# Sheet2.net
KiCad netlist of a schematic drawn in Altium Designer
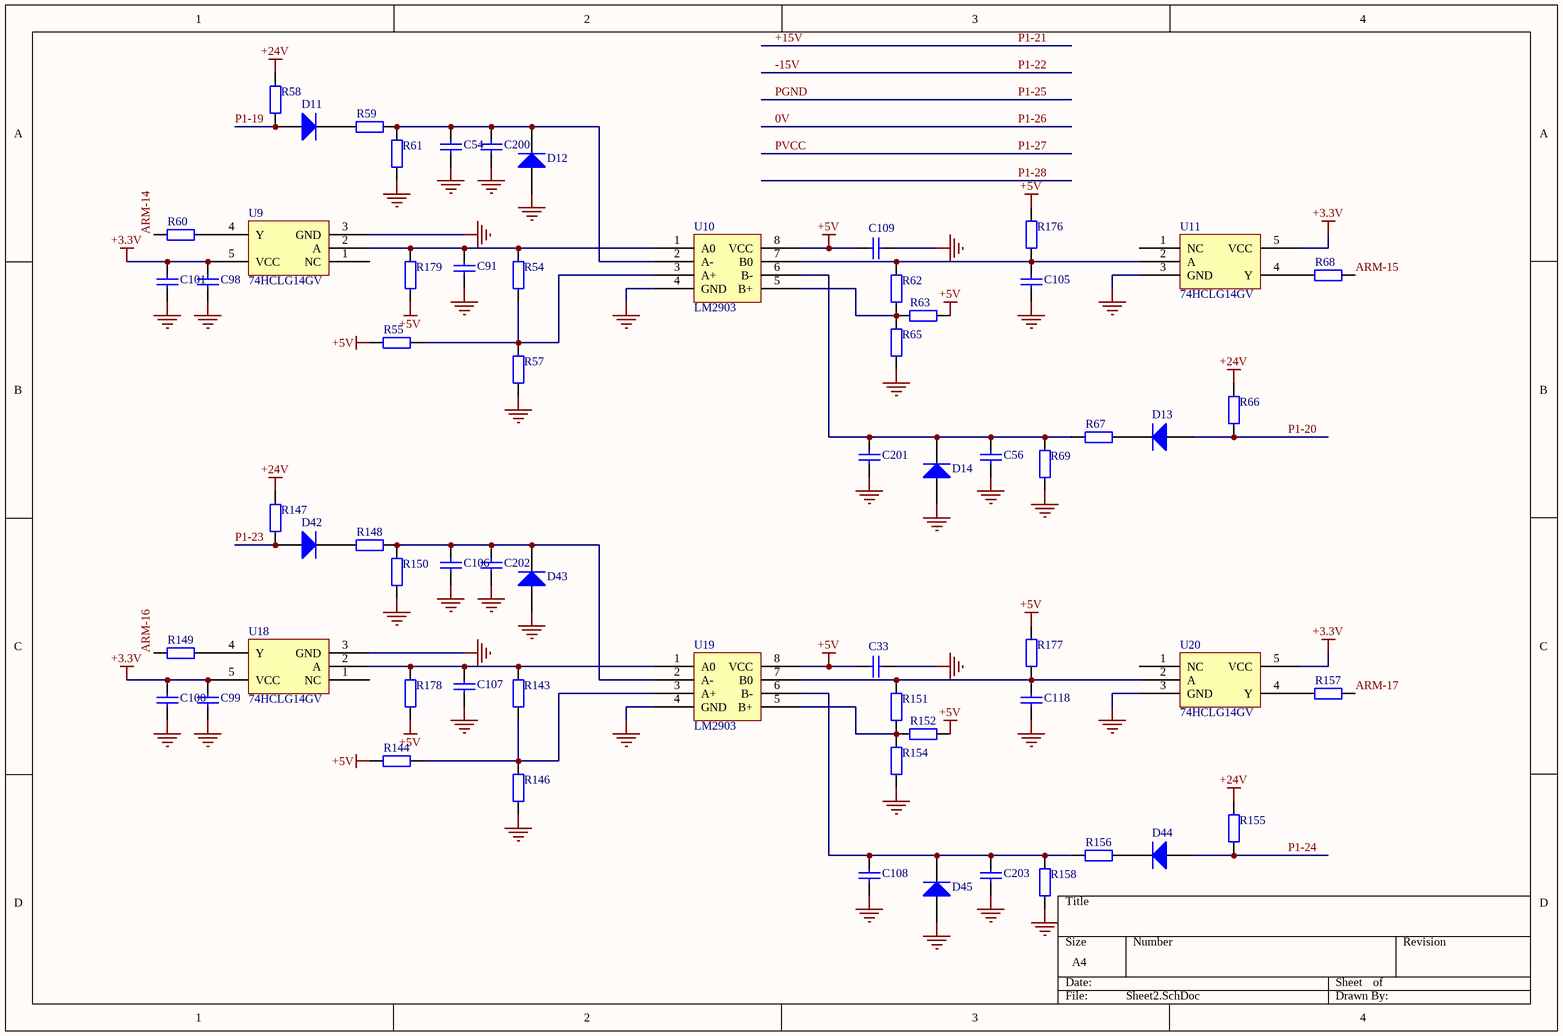
[diagram p0: Sheet2.SchDoc]

(export (version "E")
  (design (tool "Eeschema 10.0.6"))
  (components
    (comp (ref "C33")
      (value "Cap")
      (footprint "RAD-0.3")
      (description "Capacitor")
      (fields (field (name "PUBLISHER") "Altium Limited"))
      (libsource (lib "Miscellaneous Devices") (part "Cap"))
    )
    (comp (ref "C54")
      (value "Cap")
      (footprint "RAD-0.3")
      (description "Capacitor")
      (fields (field (name "PUBLISHER") "Altium Limited"))
      (libsource (lib "Miscellaneous Devices") (part "Cap"))
    )
    (comp (ref "C56")
      (value "Cap")
      (footprint "RAD-0.3")
      (description "Capacitor")
      (fields (field (name "PUBLISHER") "Altium Limited"))
      (libsource (lib "Miscellaneous Devices") (part "Cap"))
    )
    (comp (ref "C91")
      (value "Cap")
      (footprint "RAD-0.3")
      (description "Capacitor")
      (fields (field (name "PUBLISHER") "Altium Limited"))
      (libsource (lib "Miscellaneous Devices") (part "Cap"))
    )
    (comp (ref "C98")
      (value "Cap")
      (footprint "RAD-0.3")
      (description "Capacitor")
      (fields (field (name "PUBLISHER") "Altium Limited"))
      (libsource (lib "Miscellaneous Devices") (part "Cap"))
    )
    (comp (ref "C99")
      (value "Cap")
      (footprint "RAD-0.3")
      (description "Capacitor")
      (fields (field (name "PUBLISHER") "Altium Limited"))
      (libsource (lib "Miscellaneous Devices") (part "Cap"))
    )
    (comp (ref "C100")
      (value "Cap")
      (footprint "RAD-0.3")
      (description "Capacitor")
      (fields (field (name "PUBLISHER") "Altium Limited"))
      (libsource (lib "Miscellaneous Devices") (part "Cap"))
    )
    (comp (ref "C101")
      (value "Cap")
      (footprint "RAD-0.3")
      (description "Capacitor")
      (fields (field (name "PUBLISHER") "Altium Limited"))
      (libsource (lib "Miscellaneous Devices") (part "Cap"))
    )
    (comp (ref "C105")
      (value "Cap")
      (footprint "RAD-0.3")
      (description "Capacitor")
      (fields (field (name "PUBLISHER") "Altium Limited"))
      (libsource (lib "Miscellaneous Devices") (part "Cap"))
    )
    (comp (ref "C106")
      (value "Cap")
      (footprint "RAD-0.3")
      (description "Capacitor")
      (fields (field (name "PUBLISHER") "Altium Limited"))
      (libsource (lib "Miscellaneous Devices") (part "Cap"))
    )
    (comp (ref "C107")
      (value "Cap")
      (footprint "RAD-0.3")
      (description "Capacitor")
      (fields (field (name "PUBLISHER") "Altium Limited"))
      (libsource (lib "Miscellaneous Devices") (part "Cap"))
    )
    (comp (ref "C108")
      (value "Cap")
      (footprint "RAD-0.3")
      (description "Capacitor")
      (fields (field (name "PUBLISHER") "Altium Limited"))
      (libsource (lib "Miscellaneous Devices") (part "Cap"))
    )
    (comp (ref "C109")
      (value "Cap")
      (footprint "RAD-0.3")
      (description "Capacitor")
      (fields (field (name "PUBLISHER") "Altium Limited"))
      (libsource (lib "Miscellaneous Devices") (part "Cap"))
    )
    (comp (ref "C118")
      (value "Cap")
      (footprint "RAD-0.3")
      (description "Capacitor")
      (fields (field (name "PUBLISHER") "Altium Limited"))
      (libsource (lib "Miscellaneous Devices") (part "Cap"))
    )
    (comp (ref "C200")
      (value "Cap")
      (footprint "RAD-0.3")
      (description "Capacitor")
      (fields (field (name "PUBLISHER") "Altium Limited"))
      (libsource (lib "Miscellaneous Devices") (part "Cap"))
    )
    (comp (ref "C201")
      (value "Cap")
      (footprint "RAD-0.3")
      (description "Capacitor")
      (fields (field (name "PUBLISHER") "Altium Limited"))
      (libsource (lib "Miscellaneous Devices") (part "Cap"))
    )
    (comp (ref "C202")
      (value "Cap")
      (footprint "RAD-0.3")
      (description "Capacitor")
      (fields (field (name "PUBLISHER") "Altium Limited"))
      (libsource (lib "Miscellaneous Devices") (part "Cap"))
    )
    (comp (ref "C203")
      (value "Cap")
      (footprint "RAD-0.3")
      (description "Capacitor")
      (fields (field (name "PUBLISHER") "Altium Limited"))
      (libsource (lib "Miscellaneous Devices") (part "Cap"))
    )
    (comp (ref "D11")
      (value "Diode 1N4007")
      (footprint "DO-41")
      (description "1 Amp General Purpose Rectifier")
      (fields (field (name "PUBLISHER") "Altium Limited"))
      (libsource (lib "Miscellaneous Devices") (part "Diode 1N4007"))
    )
    (comp (ref "D12")
      (value "Diode 1N4007")
      (footprint "DO-41")
      (description "1 Amp General Purpose Rectifier")
      (fields (field (name "PUBLISHER") "Altium Limited"))
      (libsource (lib "Miscellaneous Devices") (part "Diode 1N4007"))
    )
    (comp (ref "D13")
      (value "Diode 1N4007")
      (footprint "DO-41")
      (description "1 Amp General Purpose Rectifier")
      (fields (field (name "PUBLISHER") "Altium Limited"))
      (libsource (lib "Miscellaneous Devices") (part "Diode 1N4007"))
    )
    (comp (ref "D14")
      (value "Diode 1N4007")
      (footprint "DO-41")
      (description "1 Amp General Purpose Rectifier")
      (fields (field (name "PUBLISHER") "Altium Limited"))
      (libsource (lib "Miscellaneous Devices") (part "Diode 1N4007"))
    )
    (comp (ref "D42")
      (value "Diode 1N4007")
      (footprint "DO-41")
      (description "1 Amp General Purpose Rectifier")
      (fields (field (name "PUBLISHER") "Altium Limited"))
      (libsource (lib "Miscellaneous Devices") (part "Diode 1N4007"))
    )
    (comp (ref "D43")
      (value "Diode 1N4007")
      (footprint "DO-41")
      (description "1 Amp General Purpose Rectifier")
      (fields (field (name "PUBLISHER") "Altium Limited"))
      (libsource (lib "Miscellaneous Devices") (part "Diode 1N4007"))
    )
    (comp (ref "D44")
      (value "Diode 1N4007")
      (footprint "DO-41")
      (description "1 Amp General Purpose Rectifier")
      (fields (field (name "PUBLISHER") "Altium Limited"))
      (libsource (lib "Miscellaneous Devices") (part "Diode 1N4007"))
    )
    (comp (ref "D45")
      (value "Diode 1N4007")
      (footprint "DO-41")
      (description "1 Amp General Purpose Rectifier")
      (fields (field (name "PUBLISHER") "Altium Limited"))
      (libsource (lib "Miscellaneous Devices") (part "Diode 1N4007"))
    )
    (comp (ref "R54")
      (value "Res2")
      (footprint "AXIAL-0.4")
      (description "Resistor")
      (fields (field (name "PUBLISHER") "Altium Limited"))
      (libsource (lib "") (part "Res2_1"))
    )
    (comp (ref "R55")
      (value "Res2")
      (footprint "AXIAL-0.4")
      (description "Resistor")
      (fields (field (name "PUBLISHER") "Altium Limited"))
      (libsource (lib "") (part "Res2_2"))
    )
    (comp (ref "R57")
      (value "Res2")
      (footprint "AXIAL-0.4")
      (description "Resistor")
      (fields (field (name "PUBLISHER") "Altium Limited"))
      (libsource (lib "Miscellaneous Devices") (part "Res2"))
    )
    (comp (ref "R58")
      (value "Res2")
      (footprint "AXIAL-0.4")
      (description "Resistor")
      (fields (field (name "PUBLISHER") "Altium Limited"))
      (libsource (lib "") (part "Res2_1"))
    )
    (comp (ref "R59")
      (value "Res2")
      (footprint "AXIAL-0.4")
      (description "Resistor")
      (fields (field (name "PUBLISHER") "Altium Limited"))
      (libsource (lib "") (part "Res2_2"))
    )
    (comp (ref "R60")
      (value "Res2")
      (footprint "AXIAL-0.4")
      (description "Resistor")
      (fields (field (name "PUBLISHER") "Altium Limited"))
      (libsource (lib "") (part "Res2_3"))
    )
    (comp (ref "R61")
      (value "Res2")
      (footprint "AXIAL-0.4")
      (description "Resistor")
      (fields (field (name "PUBLISHER") "Altium Limited"))
      (libsource (lib "") (part "Res2_1"))
    )
    (comp (ref "R62")
      (value "Res2")
      (footprint "AXIAL-0.4")
      (description "Resistor")
      (fields (field (name "PUBLISHER") "Altium Limited"))
      (libsource (lib "Miscellaneous Devices") (part "Res2"))
    )
    (comp (ref "R63")
      (value "Res2")
      (footprint "AXIAL-0.4")
      (description "Resistor")
      (fields (field (name "PUBLISHER") "Altium Limited"))
      (libsource (lib "") (part "Res2_2"))
    )
    (comp (ref "R65")
      (value "Res2")
      (footprint "AXIAL-0.4")
      (description "Resistor")
      (fields (field (name "PUBLISHER") "Altium Limited"))
      (libsource (lib "Miscellaneous Devices") (part "Res2"))
    )
    (comp (ref "R66")
      (value "Res2")
      (footprint "AXIAL-0.4")
      (description "Resistor")
      (fields (field (name "PUBLISHER") "Altium Limited"))
      (libsource (lib "") (part "Res2_1"))
    )
    (comp (ref "R67")
      (value "Res2")
      (footprint "AXIAL-0.4")
      (description "Resistor")
      (fields (field (name "PUBLISHER") "Altium Limited"))
      (libsource (lib "") (part "Res2_2"))
    )
    (comp (ref "R68")
      (value "Res2")
      (footprint "AXIAL-0.4")
      (description "Resistor")
      (fields (field (name "PUBLISHER") "Altium Limited"))
      (libsource (lib "") (part "Res2_3"))
    )
    (comp (ref "R69")
      (value "Res2")
      (footprint "AXIAL-0.4")
      (description "Resistor")
      (fields (field (name "PUBLISHER") "Altium Limited"))
      (libsource (lib "") (part "Res2_1"))
    )
    (comp (ref "R143")
      (value "Res2")
      (footprint "AXIAL-0.4")
      (description "Resistor")
      (fields (field (name "PUBLISHER") "Altium Limited"))
      (libsource (lib "") (part "Res2_1"))
    )
    (comp (ref "R144")
      (value "Res2")
      (footprint "AXIAL-0.4")
      (description "Resistor")
      (fields (field (name "PUBLISHER") "Altium Limited"))
      (libsource (lib "") (part "Res2_2"))
    )
    (comp (ref "R146")
      (value "Res2")
      (footprint "AXIAL-0.4")
      (description "Resistor")
      (fields (field (name "PUBLISHER") "Altium Limited"))
      (libsource (lib "Miscellaneous Devices") (part "Res2"))
    )
    (comp (ref "R147")
      (value "Res2")
      (footprint "AXIAL-0.4")
      (description "Resistor")
      (fields (field (name "PUBLISHER") "Altium Limited"))
      (libsource (lib "") (part "Res2_1"))
    )
    (comp (ref "R148")
      (value "Res2")
      (footprint "AXIAL-0.4")
      (description "Resistor")
      (fields (field (name "PUBLISHER") "Altium Limited"))
      (libsource (lib "") (part "Res2_2"))
    )
    (comp (ref "R149")
      (value "Res2")
      (footprint "AXIAL-0.4")
      (description "Resistor")
      (fields (field (name "PUBLISHER") "Altium Limited"))
      (libsource (lib "") (part "Res2_3"))
    )
    (comp (ref "R150")
      (value "Res2")
      (footprint "AXIAL-0.4")
      (description "Resistor")
      (fields (field (name "PUBLISHER") "Altium Limited"))
      (libsource (lib "") (part "Res2_1"))
    )
    (comp (ref "R151")
      (value "Res2")
      (footprint "AXIAL-0.4")
      (description "Resistor")
      (fields (field (name "PUBLISHER") "Altium Limited"))
      (libsource (lib "Miscellaneous Devices") (part "Res2"))
    )
    (comp (ref "R152")
      (value "Res2")
      (footprint "AXIAL-0.4")
      (description "Resistor")
      (fields (field (name "PUBLISHER") "Altium Limited"))
      (libsource (lib "") (part "Res2_2"))
    )
    (comp (ref "R154")
      (value "Res2")
      (footprint "AXIAL-0.4")
      (description "Resistor")
      (fields (field (name "PUBLISHER") "Altium Limited"))
      (libsource (lib "Miscellaneous Devices") (part "Res2"))
    )
    (comp (ref "R155")
      (value "Res2")
      (footprint "AXIAL-0.4")
      (description "Resistor")
      (fields (field (name "PUBLISHER") "Altium Limited"))
      (libsource (lib "") (part "Res2_1"))
    )
    (comp (ref "R156")
      (value "Res2")
      (footprint "AXIAL-0.4")
      (description "Resistor")
      (fields (field (name "PUBLISHER") "Altium Limited"))
      (libsource (lib "") (part "Res2_2"))
    )
    (comp (ref "R157")
      (value "Res2")
      (footprint "AXIAL-0.4")
      (description "Resistor")
      (fields (field (name "PUBLISHER") "Altium Limited"))
      (libsource (lib "") (part "Res2_3"))
    )
    (comp (ref "R158")
      (value "Res2")
      (footprint "AXIAL-0.4")
      (description "Resistor")
      (fields (field (name "PUBLISHER") "Altium Limited"))
      (libsource (lib "") (part "Res2_1"))
    )
    (comp (ref "R176")
      (value "Res2")
      (footprint "AXIAL-0.4")
      (description "Resistor")
      (fields (field (name "PUBLISHER") "Altium Limited"))
      (libsource (lib "Miscellaneous Devices") (part "Res2"))
    )
    (comp (ref "R177")
      (value "Res2")
      (footprint "AXIAL-0.4")
      (description "Resistor")
      (fields (field (name "PUBLISHER") "Altium Limited"))
      (libsource (lib "Miscellaneous Devices") (part "Res2"))
    )
    (comp (ref "R178")
      (value "Res2")
      (footprint "AXIAL-0.4")
      (description "Resistor")
      (fields (field (name "PUBLISHER") "Altium Limited"))
      (libsource (lib "Miscellaneous Devices") (part "Res2"))
    )
    (comp (ref "R179")
      (value "Res2")
      (footprint "AXIAL-0.4")
      (description "Resistor")
      (fields (field (name "PUBLISHER") "Altium Limited"))
      (libsource (lib "Miscellaneous Devices") (part "Res2"))
    )
    (comp (ref "U9") (value "74HCLG14GV") (libsource (lib "Schlib1") (part "Component_1")))
    (comp (ref "U10") (value "LM2903") (libsource (lib "LM2903") (part "Component_1")))
    (comp (ref "U11") (value "74HCLG14GV") (libsource (lib "") (part "Component_1_1")))
    (comp (ref "U18") (value "74HCLG14GV") (libsource (lib "Schlib1") (part "Component_1")))
    (comp (ref "U19") (value "LM2903") (libsource (lib "LM2903") (part "Component_1")))
    (comp (ref "U20") (value "74HCLG14GV") (libsource (lib "") (part "Component_1_1")))
  )
  (nets
    (net (code "1") (name "+3.3V") (class "Default")
      (node (ref "C100") (pin "2") (pinfunction "2_2") (pintype "passive"))
      (node (ref "C101") (pin "2") (pinfunction "2_2") (pintype "passive"))
      (node (ref "C98") (pin "2") (pinfunction "2_2") (pintype "passive"))
      (node (ref "C99") (pin "2") (pinfunction "2_2") (pintype "passive"))
      (node (ref "U11") (pin "5") (pinfunction "VCC_5") (pintype "passive"))
      (node (ref "U18") (pin "5") (pinfunction "VCC_5") (pintype "passive"))
      (node (ref "U20") (pin "5") (pinfunction "VCC_5") (pintype "passive"))
      (node (ref "U9") (pin "5") (pinfunction "VCC_5") (pintype "passive"))
    )
    (net (code "2") (name "+5V") (class "Default")
      (node (ref "C109") (pin "2") (pinfunction "2_2") (pintype "passive"))
      (node (ref "C33") (pin "2") (pinfunction "2_2") (pintype "passive"))
      (node (ref "R144") (pin "2") (pinfunction "2_2") (pintype "passive"))
      (node (ref "R152") (pin "1") (pinfunction "1_1") (pintype "passive"))
      (node (ref "R176") (pin "1") (pinfunction "1_1") (pintype "passive"))
      (node (ref "R177") (pin "1") (pinfunction "1_1") (pintype "passive"))
      (node (ref "R178") (pin "2") (pinfunction "2_2") (pintype "passive"))
      (node (ref "R179") (pin "2") (pinfunction "2_2") (pintype "passive"))
      (node (ref "R55") (pin "2") (pinfunction "2_2") (pintype "passive"))
      (node (ref "R63") (pin "1") (pinfunction "1_1") (pintype "passive"))
      (node (ref "U10") (pin "8") (pinfunction "VCC_8") (pintype "passive"))
      (node (ref "U19") (pin "8") (pinfunction "VCC_8") (pintype "passive"))
    )
    (net (code "3") (name "+24V") (class "Default")
      (node (ref "R147") (pin "2") (pinfunction "2_2") (pintype "passive"))
      (node (ref "R155") (pin "2") (pinfunction "2_2") (pintype "passive"))
      (node (ref "R58") (pin "2") (pinfunction "2_2") (pintype "passive"))
      (node (ref "R66") (pin "2") (pinfunction "2_2") (pintype "passive"))
    )
    (net (code "7") (name "/ARM-14") (class "Default")
      (node (ref "R60") (pin "1") (pinfunction "1_1") (pintype "passive"))
    )
    (net (code "8") (name "/ARM-15") (class "Default")
      (node (ref "R68") (pin "2") (pinfunction "2_2") (pintype "passive"))
    )
    (net (code "9") (name "/ARM-16") (class "Default")
      (node (ref "R149") (pin "1") (pinfunction "1_1") (pintype "passive"))
    )
    (net (code "10") (name "/ARM-17") (class "Default")
      (node (ref "R157") (pin "2") (pinfunction "2_2") (pintype "passive"))
    )
    (net (code "11") (name "/P1-19") (class "Default")
      (node (ref "D11") (pin "1") (pinfunction "A_1") (pintype "passive"))
      (node (ref "R58") (pin "1") (pinfunction "1_1") (pintype "passive"))
    )
    (net (code "12") (name "/P1-20") (class "Default")
      (node (ref "D13") (pin "1") (pinfunction "A_1") (pintype "passive"))
      (node (ref "R66") (pin "1") (pinfunction "1_1") (pintype "passive"))
    )
    (net (code "13") (name "/P1-23") (class "Default")
      (node (ref "D42") (pin "1") (pinfunction "A_1") (pintype "passive"))
      (node (ref "R147") (pin "1") (pinfunction "1_1") (pintype "passive"))
    )
    (net (code "14") (name "/P1-24") (class "Default")
      (node (ref "D44") (pin "1") (pinfunction "A_1") (pintype "passive"))
      (node (ref "R155") (pin "1") (pinfunction "1_1") (pintype "passive"))
    )
    (net (code "18") (name "GND") (class "Default")
      (node (ref "C100") (pin "1") (pinfunction "1_1") (pintype "passive"))
      (node (ref "C101") (pin "1") (pinfunction "1_1") (pintype "passive"))
      (node (ref "C105") (pin "2") (pinfunction "2_2") (pintype "passive"))
      (node (ref "C106") (pin "1") (pinfunction "1_1") (pintype "passive"))
      (node (ref "C107") (pin "1") (pinfunction "1_1") (pintype "passive"))
      (node (ref "C108") (pin "2") (pinfunction "2_2") (pintype "passive"))
      (node (ref "C109") (pin "1") (pinfunction "1_1") (pintype "passive"))
      (node (ref "C118") (pin "2") (pinfunction "2_2") (pintype "passive"))
      (node (ref "C200") (pin "1") (pinfunction "1_1") (pintype "passive"))
      (node (ref "C201") (pin "2") (pinfunction "2_2") (pintype "passive"))
      (node (ref "C202") (pin "1") (pinfunction "1_1") (pintype "passive"))
      (node (ref "C203") (pin "2") (pinfunction "2_2") (pintype "passive"))
      (node (ref "C33") (pin "1") (pinfunction "1_1") (pintype "passive"))
      (node (ref "C54") (pin "1") (pinfunction "1_1") (pintype "passive"))
      (node (ref "C56") (pin "2") (pinfunction "2_2") (pintype "passive"))
      (node (ref "C91") (pin "1") (pinfunction "1_1") (pintype "passive"))
      (node (ref "C98") (pin "1") (pinfunction "1_1") (pintype "passive"))
      (node (ref "C99") (pin "1") (pinfunction "1_1") (pintype "passive"))
      (node (ref "D12") (pin "1") (pinfunction "A_1") (pintype "passive"))
      (node (ref "D14") (pin "1") (pinfunction "A_1") (pintype "passive"))
      (node (ref "D43") (pin "1") (pinfunction "A_1") (pintype "passive"))
      (node (ref "D45") (pin "1") (pinfunction "A_1") (pintype "passive"))
      (node (ref "R146") (pin "2") (pinfunction "2_2") (pintype "passive"))
      (node (ref "R150") (pin "1") (pinfunction "1_1") (pintype "passive"))
      (node (ref "R154") (pin "2") (pinfunction "2_2") (pintype "passive"))
      (node (ref "R158") (pin "1") (pinfunction "1_1") (pintype "passive"))
      (node (ref "R57") (pin "2") (pinfunction "2_2") (pintype "passive"))
      (node (ref "R61") (pin "1") (pinfunction "1_1") (pintype "passive"))
      (node (ref "R65") (pin "2") (pinfunction "2_2") (pintype "passive"))
      (node (ref "R69") (pin "1") (pinfunction "1_1") (pintype "passive"))
      (node (ref "U10") (pin "4") (pinfunction "GND_4") (pintype "passive"))
      (node (ref "U11") (pin "3") (pinfunction "GND_3") (pintype "passive"))
      (node (ref "U18") (pin "3") (pinfunction "GND_3") (pintype "passive"))
      (node (ref "U19") (pin "4") (pinfunction "GND_4") (pintype "passive"))
      (node (ref "U20") (pin "3") (pinfunction "GND_3") (pintype "passive"))
      (node (ref "U9") (pin "3") (pinfunction "GND_3") (pintype "passive"))
    )
    (net (code "19") (name "Net-(D11-K)") (class "Default")
      (node (ref "D11") (pin "2") (pinfunction "K_2") (pintype "passive"))
      (node (ref "R59") (pin "2") (pinfunction "2_2") (pintype "passive"))
    )
    (net (code "20") (name "Net-(D12-K)") (class "Default")
      (node (ref "C200") (pin "2") (pinfunction "2_2") (pintype "passive"))
      (node (ref "C54") (pin "2") (pinfunction "2_2") (pintype "passive"))
      (node (ref "D12") (pin "2") (pinfunction "K_2") (pintype "passive"))
      (node (ref "R59") (pin "1") (pinfunction "1_1") (pintype "passive"))
      (node (ref "R61") (pin "2") (pinfunction "2_2") (pintype "passive"))
      (node (ref "U10") (pin "2") (pinfunction "A-_2") (pintype "passive"))
    )
    (net (code "21") (name "Net-(D13-K)") (class "Default")
      (node (ref "D13") (pin "2") (pinfunction "K_2") (pintype "passive"))
      (node (ref "R67") (pin "1") (pinfunction "1_1") (pintype "passive"))
    )
    (net (code "22") (name "Net-(D14-K)") (class "Default")
      (node (ref "C201") (pin "1") (pinfunction "1_1") (pintype "passive"))
      (node (ref "C56") (pin "1") (pinfunction "1_1") (pintype "passive"))
      (node (ref "D14") (pin "2") (pinfunction "K_2") (pintype "passive"))
      (node (ref "R67") (pin "2") (pinfunction "2_2") (pintype "passive"))
      (node (ref "R69") (pin "2") (pinfunction "2_2") (pintype "passive"))
      (node (ref "U10") (pin "6") (pinfunction "B-_6") (pintype "passive"))
    )
    (net (code "23") (name "Net-(D42-K)") (class "Default")
      (node (ref "D42") (pin "2") (pinfunction "K_2") (pintype "passive"))
      (node (ref "R148") (pin "2") (pinfunction "2_2") (pintype "passive"))
    )
    (net (code "24") (name "Net-(D43-K)") (class "Default")
      (node (ref "C106") (pin "2") (pinfunction "2_2") (pintype "passive"))
      (node (ref "C202") (pin "2") (pinfunction "2_2") (pintype "passive"))
      (node (ref "D43") (pin "2") (pinfunction "K_2") (pintype "passive"))
      (node (ref "R148") (pin "1") (pinfunction "1_1") (pintype "passive"))
      (node (ref "R150") (pin "2") (pinfunction "2_2") (pintype "passive"))
      (node (ref "U19") (pin "2") (pinfunction "A-_2") (pintype "passive"))
    )
    (net (code "25") (name "Net-(D44-K)") (class "Default")
      (node (ref "D44") (pin "2") (pinfunction "K_2") (pintype "passive"))
      (node (ref "R156") (pin "1") (pinfunction "1_1") (pintype "passive"))
    )
    (net (code "26") (name "Net-(D45-K)") (class "Default")
      (node (ref "C108") (pin "1") (pinfunction "1_1") (pintype "passive"))
      (node (ref "C203") (pin "1") (pinfunction "1_1") (pintype "passive"))
      (node (ref "D45") (pin "2") (pinfunction "K_2") (pintype "passive"))
      (node (ref "R156") (pin "2") (pinfunction "2_2") (pintype "passive"))
      (node (ref "R158") (pin "2") (pinfunction "2_2") (pintype "passive"))
      (node (ref "U19") (pin "6") (pinfunction "B-_6") (pintype "passive"))
    )
    (net (code "27") (name "Net-(U9-Y)") (class "Default")
      (node (ref "R60") (pin "2") (pinfunction "2_2") (pintype "passive"))
      (node (ref "U9") (pin "4") (pinfunction "Y_4") (pintype "passive"))
    )
    (net (code "28") (name "Net-(U10-A+)") (class "Default")
      (node (ref "R54") (pin "1") (pinfunction "1_1") (pintype "passive"))
      (node (ref "R55") (pin "1") (pinfunction "1_1") (pintype "passive"))
      (node (ref "R57") (pin "1") (pinfunction "1_1") (pintype "passive"))
      (node (ref "U10") (pin "3") (pinfunction "A+_3") (pintype "passive"))
    )
    (net (code "29") (name "Net-(U10-A0)") (class "Default")
      (node (ref "C91") (pin "2") (pinfunction "2_2") (pintype "passive"))
      (node (ref "R179") (pin "1") (pinfunction "1_1") (pintype "passive"))
      (node (ref "R54") (pin "2") (pinfunction "2_2") (pintype "passive"))
      (node (ref "U10") (pin "1") (pinfunction "A0_1") (pintype "passive"))
      (node (ref "U9") (pin "2") (pinfunction "A_2") (pintype "passive"))
    )
    (net (code "30") (name "Net-(U10-B+)") (class "Default")
      (node (ref "R62") (pin "2") (pinfunction "2_2") (pintype "passive"))
      (node (ref "R63") (pin "2") (pinfunction "2_2") (pintype "passive"))
      (node (ref "R65") (pin "1") (pinfunction "1_1") (pintype "passive"))
      (node (ref "U10") (pin "5") (pinfunction "B+_5") (pintype "passive"))
    )
    (net (code "31") (name "Net-(U10-B0)") (class "Default")
      (node (ref "C105") (pin "1") (pinfunction "1_1") (pintype "passive"))
      (node (ref "R176") (pin "2") (pinfunction "2_2") (pintype "passive"))
      (node (ref "R62") (pin "1") (pinfunction "1_1") (pintype "passive"))
      (node (ref "U10") (pin "7") (pinfunction "B0_7") (pintype "passive"))
      (node (ref "U11") (pin "2") (pinfunction "A_2") (pintype "passive"))
    )
    (net (code "32") (name "Net-(U11-Y)") (class "Default")
      (node (ref "R68") (pin "1") (pinfunction "1_1") (pintype "passive"))
      (node (ref "U11") (pin "4") (pinfunction "Y_4") (pintype "passive"))
    )
    (net (code "33") (name "Net-(U18-A)") (class "Default")
      (node (ref "C107") (pin "2") (pinfunction "2_2") (pintype "passive"))
      (node (ref "R143") (pin "2") (pinfunction "2_2") (pintype "passive"))
      (node (ref "R178") (pin "1") (pinfunction "1_1") (pintype "passive"))
      (node (ref "U18") (pin "2") (pinfunction "A_2") (pintype "passive"))
      (node (ref "U19") (pin "1") (pinfunction "A0_1") (pintype "passive"))
    )
    (net (code "34") (name "Net-(U18-Y)") (class "Default")
      (node (ref "R149") (pin "2") (pinfunction "2_2") (pintype "passive"))
      (node (ref "U18") (pin "4") (pinfunction "Y_4") (pintype "passive"))
    )
    (net (code "35") (name "Net-(U19-A+)") (class "Default")
      (node (ref "R143") (pin "1") (pinfunction "1_1") (pintype "passive"))
      (node (ref "R144") (pin "1") (pinfunction "1_1") (pintype "passive"))
      (node (ref "R146") (pin "1") (pinfunction "1_1") (pintype "passive"))
      (node (ref "U19") (pin "3") (pinfunction "A+_3") (pintype "passive"))
    )
    (net (code "36") (name "Net-(U19-B+)") (class "Default")
      (node (ref "R151") (pin "2") (pinfunction "2_2") (pintype "passive"))
      (node (ref "R152") (pin "2") (pinfunction "2_2") (pintype "passive"))
      (node (ref "R154") (pin "1") (pinfunction "1_1") (pintype "passive"))
      (node (ref "U19") (pin "5") (pinfunction "B+_5") (pintype "passive"))
    )
    (net (code "37") (name "Net-(U19-B0)") (class "Default")
      (node (ref "C118") (pin "1") (pinfunction "1_1") (pintype "passive"))
      (node (ref "R151") (pin "1") (pinfunction "1_1") (pintype "passive"))
      (node (ref "R177") (pin "2") (pinfunction "2_2") (pintype "passive"))
      (node (ref "U19") (pin "7") (pinfunction "B0_7") (pintype "passive"))
      (node (ref "U20") (pin "2") (pinfunction "A_2") (pintype "passive"))
    )
    (net (code "38") (name "Net-(U20-Y)") (class "Default")
      (node (ref "R157") (pin "1") (pinfunction "1_1") (pintype "passive"))
      (node (ref "U20") (pin "4") (pinfunction "Y_4") (pintype "passive"))
    )
    (net (code "39") (name "unconnected-(U9-NC-Pad1)") (class "Default")
      (node (ref "U9") (pin "1") (pinfunction "NC_1") (pintype "passive"))
    )
    (net (code "40") (name "unconnected-(U11-NC-Pad1)") (class "Default")
      (node (ref "U11") (pin "1") (pinfunction "NC_1") (pintype "passive"))
    )
    (net (code "41") (name "unconnected-(U18-NC-Pad1)") (class "Default")
      (node (ref "U18") (pin "1") (pinfunction "NC_1") (pintype "passive"))
    )
    (net (code "42") (name "unconnected-(U20-NC-Pad1)") (class "Default")
      (node (ref "U20") (pin "1") (pinfunction "NC_1") (pintype "passive"))
    )
  )
)
